# PSU.net
KiCad netlist of a schematic drawn in Altium Designer
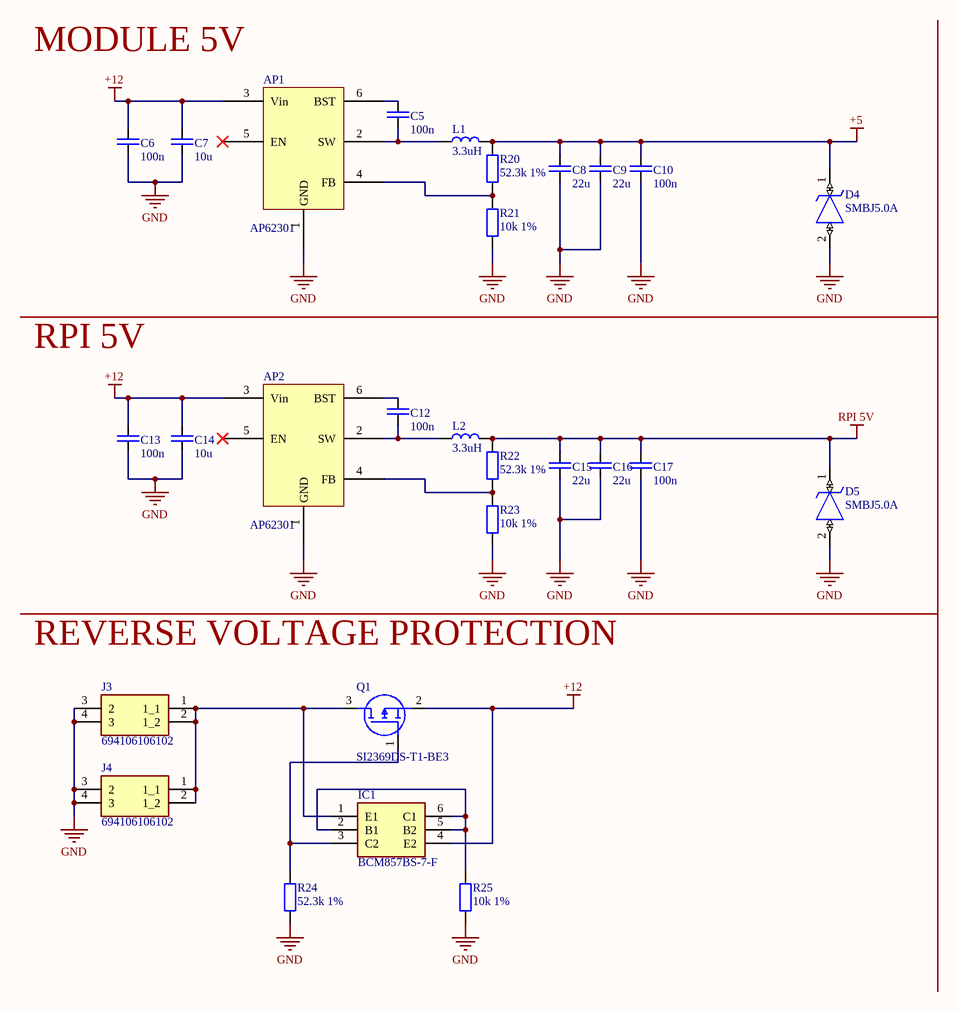
[diagram p0: PSU.SchDoc]

(export (version "E")
  (design (tool "Eeschema 10.0.6"))
  (components
    (comp (ref "AP1")
      (value "AP62301")
      (footprint "SOT95P280X100-6L")
      (libsource (lib "PiVO") (part "AP62301"))
    )
    (comp (ref "AP2")
      (value "AP62301")
      (footprint "SOT95P280X100-6L")
      (libsource (lib "PiVO") (part "AP62301"))
    )
    (comp (ref "C5")
      (value "100n")
      (footprint "C3216_1206I_L")
      (description "Capacitor")
      (libsource (lib "General") (part "C"))
    )
    (comp (ref "C6")
      (value "100n")
      (footprint "C3216_1206I_L")
      (description "Capacitor")
      (libsource (lib "General") (part "C"))
    )
    (comp (ref "C7")
      (value "10u")
      (footprint "C3225_1210I_L")
      (description "Capacitor")
      (libsource (lib "General") (part "C"))
    )
    (comp (ref "C8")
      (value "22u")
      (footprint "C3225_1210I_L")
      (description "Capacitor")
      (libsource (lib "General") (part "C"))
    )
    (comp (ref "C9")
      (value "22u")
      (footprint "C3225_1210I_L")
      (description "Capacitor")
      (libsource (lib "General") (part "C"))
    )
    (comp (ref "C10")
      (value "100n")
      (footprint "C3216_1206I_L")
      (description "Capacitor")
      (libsource (lib "General") (part "C"))
    )
    (comp (ref "C12")
      (value "100n")
      (footprint "C3216_1206I_L")
      (description "Capacitor")
      (libsource (lib "General") (part "C"))
    )
    (comp (ref "C13")
      (value "100n")
      (footprint "C3216_1206I_L")
      (description "Capacitor")
      (libsource (lib "General") (part "C"))
    )
    (comp (ref "C14")
      (value "10u")
      (footprint "C3225_1210I_L")
      (description "Capacitor")
      (libsource (lib "General") (part "C"))
    )
    (comp (ref "C15")
      (value "22u")
      (footprint "C3225_1210I_L")
      (description "Capacitor")
      (libsource (lib "General") (part "C"))
    )
    (comp (ref "C16")
      (value "22u")
      (footprint "C3225_1210I_L")
      (description "Capacitor")
      (libsource (lib "General") (part "C"))
    )
    (comp (ref "C17")
      (value "100n")
      (footprint "C3216_1206I_L")
      (description "Capacitor")
      (libsource (lib "General") (part "C"))
    )
    (comp (ref "D4")
      (value "SMBJ5.0A")
      (footprint "DIOM5436X261N")
      (description "TVS Diode (Uni-directional)")
      (fields (field (name "MOUSER PART NUMBER") "576-SMBJ5.0A"))
      (libsource (lib "components_library") (part "SMBJ5.0A"))
    )
    (comp (ref "D5")
      (value "SMBJ5.0A")
      (footprint "DIOM5436X261N")
      (description "TVS Diode (Uni-directional)")
      (fields (field (name "MOUSER PART NUMBER") "576-SMBJ5.0A"))
      (libsource (lib "components_library") (part "SMBJ5.0A"))
    )
    (comp (ref "IC1")
      (value "BCM857BS-7-F")
      (footprint "SamacSys:SOT65P210X110-6N")
      (description "Integrated Circuit")
      (fields (field (name "MOUSER PART NUMBER") "621-BCM857BS-7-F"))
      (libsource (lib "*") (part "BCM857BS-7-F"))
    )
    (comp (ref "J3")
      (value "694106106102")
      (footprint "694106106102")
      (description "Connector")
      (fields (field (name "MOUSER PART NUMBER") "710-694106106102"))
      (libsource (lib "components_library") (part "694106106102"))
    )
    (comp (ref "J4")
      (value "694106106102")
      (footprint "694106106102")
      (description "Connector")
      (fields (field (name "MOUSER PART NUMBER") "710-694106106102"))
      (libsource (lib "components_library") (part "694106106102"))
    )
    (comp (ref "L1")
      (value "3.3uH")
      (footprint "INDUCTOR_2")
      (description "L")
      (libsource (lib "General") (part "L"))
    )
    (comp (ref "L2")
      (value "3.3uH")
      (footprint "INDUCTOR_2")
      (description "L")
      (libsource (lib "General") (part "L"))
    )
    (comp (ref "Q1")
      (value "SI2369DS-T1-BE3")
      (footprint "SOT95P237X112-3N")
      (description "MOSFET (P-Channel)")
      (fields (field (name "MOUSER PART NUMBER") "78-SI2369DS-T1-BE3"))
      (libsource (lib "components_library") (part "SI2369DS-T1-BE3"))
    )
    (comp (ref "R20")
      (value "52.3k 1%")
      (footprint "R1005_0402i_L")
      (description "R")
      (libsource (lib "General") (part "R"))
    )
    (comp (ref "R21")
      (value "10k 1%")
      (footprint "R1005_0402i_L")
      (description "R")
      (libsource (lib "General") (part "R"))
    )
    (comp (ref "R22")
      (value "52.3k 1%")
      (footprint "R1005_0402i_L")
      (description "R")
      (libsource (lib "General") (part "R"))
    )
    (comp (ref "R23")
      (value "10k 1%")
      (footprint "R1005_0402i_L")
      (description "R")
      (libsource (lib "General") (part "R"))
    )
    (comp (ref "R24")
      (value "52.3k 1%")
      (footprint "R1005_0402i_L")
      (description "R")
      (libsource (lib "General") (part "R"))
    )
    (comp (ref "R25")
      (value "10k 1%")
      (footprint "R1005_0402i_L")
      (description "R")
      (libsource (lib "General") (part "R"))
    )
  )
  (nets
    (net (code "1") (name "+5") (class "Default")
      (node (ref "C10") (pin "1") (pinfunction "1_1") (pintype "passive"))
      (node (ref "C8") (pin "1") (pinfunction "1_1") (pintype "passive"))
      (node (ref "C9") (pin "1") (pinfunction "1_1") (pintype "passive"))
      (node (ref "D4") (pin "1") (pinfunction "K_1") (pintype "bidirectional"))
      (node (ref "L1") (pin "2") (pintype "passive"))
      (node (ref "R20") (pin "1") (pintype "passive"))
    )
    (net (code "2") (name "+12") (class "Default")
      (node (ref "AP1") (pin "3") (pinfunction "Vin_3") (pintype "passive"))
      (node (ref "AP2") (pin "3") (pinfunction "Vin_3") (pintype "passive"))
      (node (ref "C13") (pin "1") (pinfunction "1_1") (pintype "passive"))
      (node (ref "C14") (pin "1") (pinfunction "1_1") (pintype "passive"))
      (node (ref "C6") (pin "1") (pinfunction "1_1") (pintype "passive"))
      (node (ref "C7") (pin "1") (pinfunction "1_1") (pintype "passive"))
      (node (ref "IC1") (pin "4") (pinfunction "E2_4") (pintype "passive"))
      (node (ref "Q1") (pin "2") (pinfunction "S_2") (pintype "passive"))
    )
    (net (code "3") (name "GND") (class "Default")
      (node (ref "AP1") (pin "1") (pinfunction "GND_1") (pintype "passive"))
      (node (ref "AP2") (pin "1") (pinfunction "GND_1") (pintype "passive"))
      (node (ref "C10") (pin "2") (pinfunction "2_2") (pintype "passive"))
      (node (ref "C13") (pin "2") (pinfunction "2_2") (pintype "passive"))
      (node (ref "C14") (pin "2") (pinfunction "2_2") (pintype "passive"))
      (node (ref "C15") (pin "2") (pinfunction "2_2") (pintype "passive"))
      (node (ref "C16") (pin "2") (pinfunction "2_2") (pintype "passive"))
      (node (ref "C17") (pin "2") (pinfunction "2_2") (pintype "passive"))
      (node (ref "C6") (pin "2") (pinfunction "2_2") (pintype "passive"))
      (node (ref "C7") (pin "2") (pinfunction "2_2") (pintype "passive"))
      (node (ref "C8") (pin "2") (pinfunction "2_2") (pintype "passive"))
      (node (ref "C9") (pin "2") (pinfunction "2_2") (pintype "passive"))
      (node (ref "D4") (pin "2") (pinfunction "A_2") (pintype "bidirectional"))
      (node (ref "D5") (pin "2") (pinfunction "A_2") (pintype "bidirectional"))
      (node (ref "J3") (pin "3") (pinfunction "2_3") (pintype "passive"))
      (node (ref "J3") (pin "4") (pinfunction "3_4") (pintype "passive"))
      (node (ref "J4") (pin "3") (pinfunction "2_3") (pintype "passive"))
      (node (ref "J4") (pin "4") (pinfunction "3_4") (pintype "passive"))
      (node (ref "R21") (pin "2") (pintype "passive"))
      (node (ref "R23") (pin "2") (pintype "passive"))
      (node (ref "R24") (pin "2") (pintype "passive"))
      (node (ref "R25") (pin "2") (pintype "passive"))
    )
    (net (code "4") (name "Net-(AP1-BST)") (class "Default")
      (node (ref "AP1") (pin "6") (pinfunction "BST_6") (pintype "passive"))
      (node (ref "C5") (pin "1") (pinfunction "1_1") (pintype "passive"))
    )
    (net (code "5") (name "Net-(AP1-FB)") (class "Default")
      (node (ref "AP1") (pin "4") (pinfunction "FB_4") (pintype "passive"))
      (node (ref "R20") (pin "2") (pintype "passive"))
      (node (ref "R21") (pin "1") (pintype "passive"))
    )
    (net (code "6") (name "Net-(AP1-SW)") (class "Default")
      (node (ref "AP1") (pin "2") (pinfunction "SW_2") (pintype "passive"))
      (node (ref "C5") (pin "2") (pinfunction "2_2") (pintype "passive"))
      (node (ref "L1") (pin "1") (pintype "passive"))
    )
    (net (code "7") (name "Net-(AP2-BST)") (class "Default")
      (node (ref "AP2") (pin "6") (pinfunction "BST_6") (pintype "passive"))
      (node (ref "C12") (pin "1") (pinfunction "1_1") (pintype "passive"))
    )
    (net (code "8") (name "Net-(AP2-FB)") (class "Default")
      (node (ref "AP2") (pin "4") (pinfunction "FB_4") (pintype "passive"))
      (node (ref "R22") (pin "2") (pintype "passive"))
      (node (ref "R23") (pin "1") (pintype "passive"))
    )
    (net (code "9") (name "Net-(AP2-SW)") (class "Default")
      (node (ref "AP2") (pin "2") (pinfunction "SW_2") (pintype "passive"))
      (node (ref "C12") (pin "2") (pinfunction "2_2") (pintype "passive"))
      (node (ref "L2") (pin "1") (pintype "passive"))
    )
    (net (code "10") (name "Net-(IC1-B1)") (class "Default")
      (node (ref "IC1") (pin "2") (pinfunction "B1_2") (pintype "passive"))
      (node (ref "IC1") (pin "5") (pinfunction "B2_5") (pintype "passive"))
      (node (ref "IC1") (pin "6") (pinfunction "C1_6") (pintype "passive"))
      (node (ref "R25") (pin "1") (pintype "passive"))
    )
    (net (code "11") (name "Net-(IC1-C2)") (class "Default")
      (node (ref "IC1") (pin "3") (pinfunction "C2_3") (pintype "passive"))
      (node (ref "Q1") (pin "1") (pinfunction "G_1") (pintype "passive"))
      (node (ref "R24") (pin "1") (pintype "passive"))
    )
    (net (code "12") (name "Net-(IC1-E1)") (class "Default")
      (node (ref "IC1") (pin "1") (pinfunction "E1_1") (pintype "passive"))
      (node (ref "J3") (pin "1") (pinfunction "1_1_1") (pintype "passive"))
      (node (ref "J3") (pin "2") (pinfunction "1_2_2") (pintype "passive"))
      (node (ref "J4") (pin "1") (pinfunction "1_1_1") (pintype "passive"))
      (node (ref "J4") (pin "2") (pinfunction "1_2_2") (pintype "passive"))
      (node (ref "Q1") (pin "3") (pinfunction "D_3") (pintype "passive"))
    )
    (net (code "13") (name "RPI 5V") (class "Default")
      (node (ref "C15") (pin "1") (pinfunction "1_1") (pintype "passive"))
      (node (ref "C16") (pin "1") (pinfunction "1_1") (pintype "passive"))
      (node (ref "C17") (pin "1") (pinfunction "1_1") (pintype "passive"))
      (node (ref "D5") (pin "1") (pinfunction "K_1") (pintype "bidirectional"))
      (node (ref "L2") (pin "2") (pintype "passive"))
      (node (ref "R22") (pin "1") (pintype "passive"))
    )
    (net (code "14") (name "unconnected-(AP1-EN-Pad5)") (class "Default")
      (node (ref "AP1") (pin "5") (pinfunction "EN_5") (pintype "passive+no_connect"))
    )
    (net (code "15") (name "unconnected-(AP2-EN-Pad5)") (class "Default")
      (node (ref "AP2") (pin "5") (pinfunction "EN_5") (pintype "passive+no_connect"))
    )
  )
)
